# Sheet1.net
KiCad netlist of a schematic drawn in Altium Designer
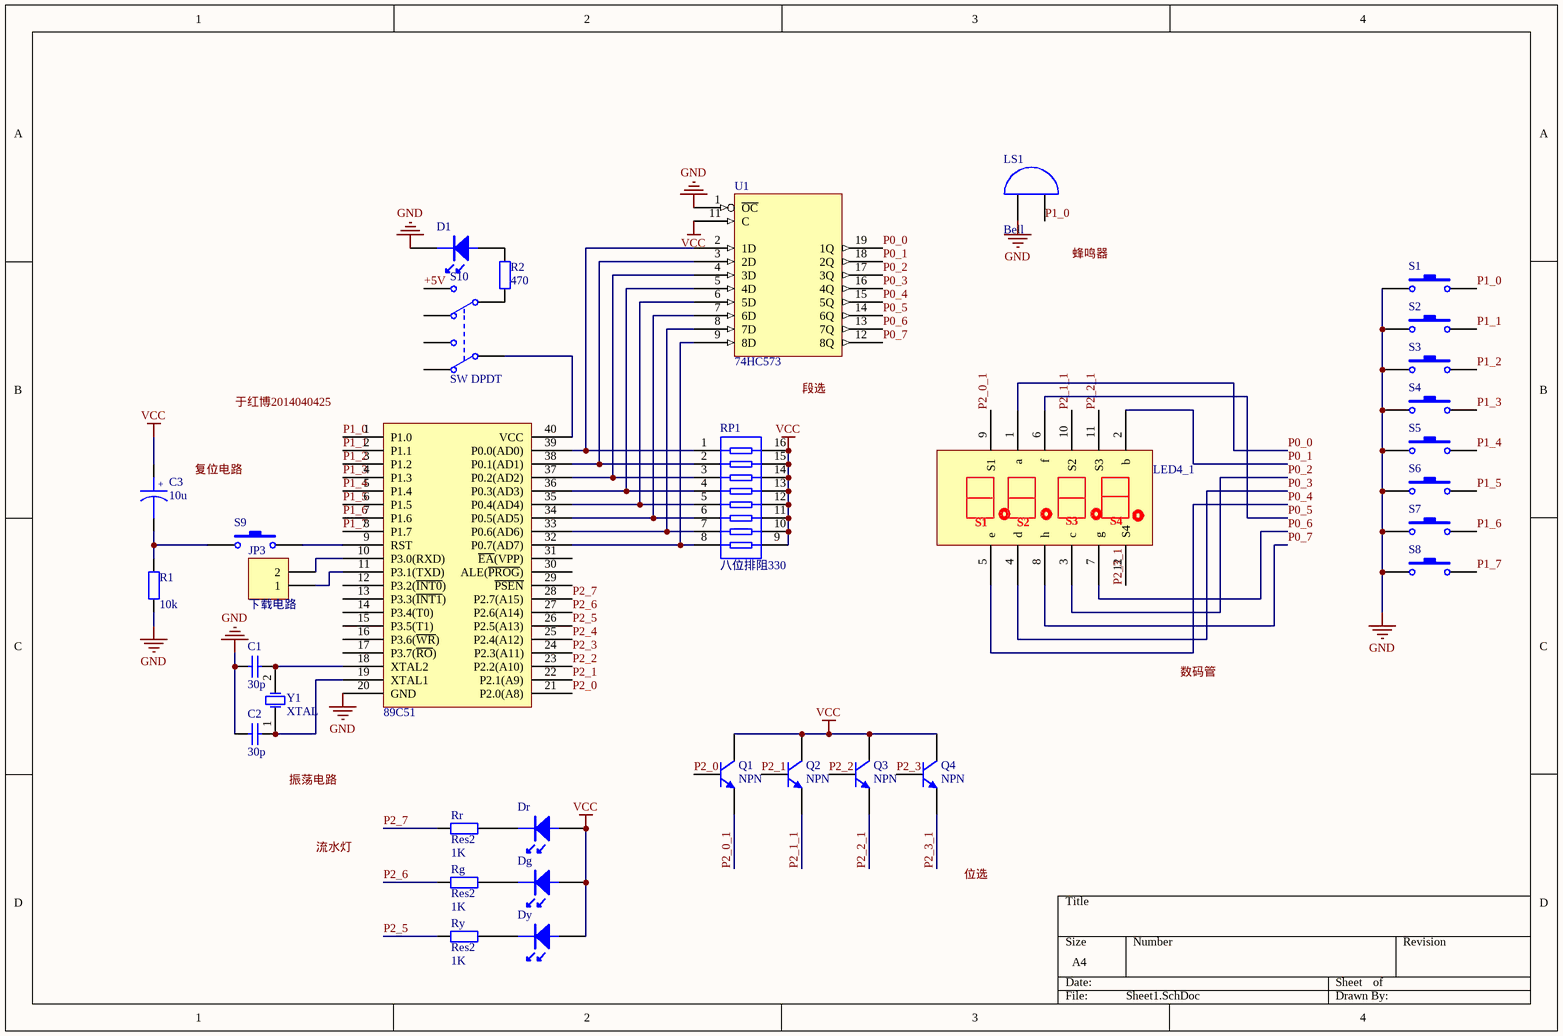
[diagram p0: Sheet1.SchDoc]

(export (version "E")
  (design (tool "Eeschema 10.0.6"))
  (components
    (comp (ref "89c51") (value "89C51") (footprint "DIP40") (libsource (lib "51单片机") (part "89C51")))
    (comp (ref "C1")
      (value "30p")
      (footprint "RAD-0.3")
      (description "Capacitor")
      (fields (field (name "PUBLISHER") "Altium Limited"))
      (libsource (lib "Miscellaneous Devices") (part "Cap"))
    )
    (comp (ref "C2")
      (value "30p")
      (footprint "RAD-0.3")
      (description "Capacitor")
      (fields (field (name "PUBLISHER") "Altium Limited"))
      (libsource (lib "Miscellaneous Devices") (part "Cap"))
    )
    (comp (ref "C3")
      (value "10u")
      (footprint "cap")
      (description "Capacitor")
      (libsource (lib "Integrated_Library1") (part "电解电容"))
    )
    (comp (ref "D1") (value "发光二极管") (footprint "DIODE0.4A") (libsource (lib "二极管") (part "发光二极管")))
    (comp (ref "Dg") (value "发光二极管阵列") (footprint "DIODE0.4A") (libsource (lib "二极管") (part "发光二极管")))
    (comp (ref "Dr") (value "发光二极管阵列") (footprint "DIODE0.4A") (libsource (lib "二极管") (part "发光二极管")))
    (comp (ref "Dy") (value "发光二极管阵列") (footprint "DIODE0.4A") (libsource (lib "二极管") (part "发光二极管")))
    (comp (ref "JP3")
      (value "下载电路")
      (footprint "HDR1X2")
      (description "Header, 2-Pin")
      (fields (field (name "PUBLISHER") "Altium Limited"))
      (libsource (lib "Miscellaneous Connectors") (part "Header 2"))
    )
    (comp (ref "led4") (value "LED4_1") (footprint "HDR2X6") (libsource (lib "数码管") (part "LED4_LWQ")))
    (comp (ref "LS1")
      (value "Bell")
      (footprint "PIN2")
      (description "Electrical Bell")
      (fields (field (name "PUBLISHER") "Altium Limited"))
      (libsource (lib "Miscellaneous Devices") (part "Bell"))
    )
    (comp (ref "Q1")
      (value "NPN")
      (footprint "TO-226-AA")
      (description "NPN Bipolar Transistor")
      (fields (field (name "PUBLISHER") "Altium Limited"))
      (libsource (lib "Miscellaneous Devices") (part "NPN"))
    )
    (comp (ref "Q2")
      (value "NPN")
      (footprint "TO-226-AA")
      (description "NPN Bipolar Transistor")
      (fields (field (name "PUBLISHER") "Altium Limited"))
      (libsource (lib "Miscellaneous Devices") (part "NPN"))
    )
    (comp (ref "Q3")
      (value "NPN")
      (footprint "TO-226-AA")
      (description "NPN Bipolar Transistor")
      (fields (field (name "PUBLISHER") "Altium Limited"))
      (libsource (lib "Miscellaneous Devices") (part "NPN"))
    )
    (comp (ref "Q4")
      (value "NPN")
      (footprint "TO-226-AA")
      (description "NPN Bipolar Transistor")
      (fields (field (name "PUBLISHER") "Altium Limited"))
      (libsource (lib "Miscellaneous Devices") (part "NPN"))
    )
    (comp (ref "R1")
      (value "10k")
      (footprint "AXIAL-0.4")
      (description "Resistor")
      (fields (field (name "Comment") "R1") (field (name "PUBLISHER") "Altium Limited"))
      (libsource (lib "") (part "Res2_1"))
    )
    (comp (ref "R2")
      (value "470")
      (footprint "AXIAL-0.4")
      (description "Resistor")
      (fields (field (name "PUBLISHER") "Altium Limited"))
      (libsource (lib "") (part "Res2_2"))
    )
    (comp (ref "Rg")
      (value "Res2")
      (footprint "AXIAL-0.4")
      (description "Resistor")
      (fields (field (name "ALTIUM_VALUE") "1K") (field (name "PUBLISHER") "Altium Limited"))
      (libsource (lib "Miscellaneous Devices") (part "Res2"))
    )
    (comp (ref "RP1") (value "八位排阻330") (footprint "DIP16") (libsource (lib "电阻") (part "RESPACK4")))
    (comp (ref "Rr")
      (value "Res2")
      (footprint "AXIAL-0.4")
      (description "Resistor")
      (fields (field (name "ALTIUM_VALUE") "1K") (field (name "PUBLISHER") "Altium Limited"))
      (libsource (lib "Miscellaneous Devices") (part "Res2"))
    )
    (comp (ref "Ry")
      (value "Res2")
      (footprint "AXIAL-0.4")
      (description "Resistor")
      (fields (field (name "ALTIUM_VALUE") "1K") (field (name "PUBLISHER") "Altium Limited"))
      (libsource (lib "Miscellaneous Devices") (part "Res2"))
    )
    (comp (ref "S1")
      (value "SW-PB")
      (footprint "SPST-2")
      (description "Switch")
      (fields (field (name "PUBLISHER") "Altium Limited"))
      (libsource (lib "Miscellaneous Devices") (part "SW-PB"))
    )
    (comp (ref "S2")
      (value "SW-PB")
      (footprint "SPST-2")
      (description "Switch")
      (fields (field (name "PUBLISHER") "Altium Limited"))
      (libsource (lib "Miscellaneous Devices") (part "SW-PB"))
    )
    (comp (ref "S3")
      (value "SW-PB")
      (footprint "SPST-2")
      (description "Switch")
      (fields (field (name "PUBLISHER") "Altium Limited"))
      (libsource (lib "Miscellaneous Devices") (part "SW-PB"))
    )
    (comp (ref "S4")
      (value "SW-PB")
      (footprint "SPST-2")
      (description "Switch")
      (fields (field (name "PUBLISHER") "Altium Limited"))
      (libsource (lib "Miscellaneous Devices") (part "SW-PB"))
    )
    (comp (ref "S5")
      (value "SW-PB")
      (footprint "SPST-2")
      (description "Switch")
      (fields (field (name "PUBLISHER") "Altium Limited"))
      (libsource (lib "Miscellaneous Devices") (part "SW-PB"))
    )
    (comp (ref "S6")
      (value "SW-PB")
      (footprint "SPST-2")
      (description "Switch")
      (fields (field (name "PUBLISHER") "Altium Limited"))
      (libsource (lib "Miscellaneous Devices") (part "SW-PB"))
    )
    (comp (ref "S7")
      (value "SW-PB")
      (footprint "SPST-2")
      (description "Switch")
      (fields (field (name "PUBLISHER") "Altium Limited"))
      (libsource (lib "Miscellaneous Devices") (part "SW-PB"))
    )
    (comp (ref "S8")
      (value "SW-PB")
      (footprint "SPST-2")
      (description "Switch")
      (fields (field (name "PUBLISHER") "Altium Limited"))
      (libsource (lib "Miscellaneous Devices") (part "SW-PB"))
    )
    (comp (ref "S9")
      (value "SW-PB")
      (footprint "SPST-2")
      (description "Switch")
      (fields (field (name "PUBLISHER") "Altium Limited"))
      (libsource (lib "Miscellaneous Devices") (part "SW-PB"))
    )
    (comp (ref "S10")
      (value "SW DPDT")
      (footprint "SOT23-6_N")
      (description "Switch")
      (fields (field (name "PUBLISHER") "Altium Limited"))
      (libsource (lib "Miscellaneous Devices") (part "SW DPDT"))
    )
    (comp (ref "U1") (value "74HC573") (footprint "DIP-20") (libsource (lib "TTL74系列IC") (part "74HC573")))
    (comp (ref "Y1")
      (value "XTAL")
      (footprint "R38")
      (description "Crystal Oscillator")
      (fields (field (name "PUBLISHER") "Altium Limited"))
      (libsource (lib "Miscellaneous Devices") (part "XTAL"))
    )
  )
  (nets
    (net (code "1") (name "/+5V") (class "Default")
      (node (ref "S10") (pin "6") (pinfunction "NO2_6") (pintype "passive"))
    )
    (net (code "2") (name "/P0_0") (class "Default")
      (node (ref "U1") (pin "19") (pinfunction "1Q_19") (pintype "output"))
      (node (ref "led4") (pin "1") (pinfunction "a_1") (pintype "passive"))
    )
    (net (code "3") (name "/P0_1") (class "Default")
      (node (ref "U1") (pin "18") (pinfunction "2Q_18") (pintype "output"))
      (node (ref "led4") (pin "2") (pinfunction "b_2") (pintype "passive"))
    )
    (net (code "4") (name "/P0_2") (class "Default")
      (node (ref "U1") (pin "17") (pinfunction "3Q_17") (pintype "output"))
      (node (ref "led4") (pin "3") (pinfunction "c_3") (pintype "passive"))
    )
    (net (code "5") (name "/P0_3") (class "Default")
      (node (ref "U1") (pin "16") (pinfunction "4Q_16") (pintype "output"))
      (node (ref "led4") (pin "4") (pinfunction "d_4") (pintype "passive"))
    )
    (net (code "6") (name "/P0_4") (class "Default")
      (node (ref "U1") (pin "15") (pinfunction "5Q_15") (pintype "output"))
      (node (ref "led4") (pin "5") (pinfunction "e_5") (pintype "passive"))
    )
    (net (code "7") (name "/P0_5") (class "Default")
      (node (ref "U1") (pin "14") (pinfunction "6Q_14") (pintype "output"))
      (node (ref "led4") (pin "6") (pinfunction "f_6") (pintype "passive"))
    )
    (net (code "8") (name "/P0_6") (class "Default")
      (node (ref "U1") (pin "13") (pinfunction "7Q_13") (pintype "output"))
      (node (ref "led4") (pin "7") (pinfunction "g_7") (pintype "passive"))
    )
    (net (code "9") (name "/P0_7") (class "Default")
      (node (ref "U1") (pin "12") (pinfunction "8Q_12") (pintype "output"))
      (node (ref "led4") (pin "8") (pinfunction "h_8") (pintype "passive"))
    )
    (net (code "10") (name "/P1_0") (class "Default")
      (node (ref "89c51") (pin "1") (pinfunction "P1.0_1") (pintype "passive"))
      (node (ref "LS1") (pin "2") (pinfunction "B_2") (pintype "passive"))
      (node (ref "S1") (pin "2") (pinfunction "2_2") (pintype "passive"))
    )
    (net (code "11") (name "/P1_1") (class "Default")
      (node (ref "89c51") (pin "2") (pinfunction "P1.1_2") (pintype "passive"))
      (node (ref "S2") (pin "2") (pinfunction "2_2") (pintype "passive"))
    )
    (net (code "12") (name "/P1_2") (class "Default")
      (node (ref "89c51") (pin "3") (pinfunction "P1.2_3") (pintype "passive"))
      (node (ref "S3") (pin "2") (pinfunction "2_2") (pintype "passive"))
    )
    (net (code "13") (name "/P1_3") (class "Default")
      (node (ref "89c51") (pin "4") (pinfunction "P1.3_4") (pintype "passive"))
      (node (ref "S4") (pin "2") (pinfunction "2_2") (pintype "passive"))
    )
    (net (code "14") (name "/P1_4") (class "Default")
      (node (ref "89c51") (pin "5") (pinfunction "P1.4_5") (pintype "passive"))
      (node (ref "S5") (pin "2") (pinfunction "2_2") (pintype "passive"))
    )
    (net (code "15") (name "/P1_5") (class "Default")
      (node (ref "89c51") (pin "6") (pinfunction "P1.5_6") (pintype "passive"))
      (node (ref "S6") (pin "2") (pinfunction "2_2") (pintype "passive"))
    )
    (net (code "16") (name "/P1_6") (class "Default")
      (node (ref "89c51") (pin "7") (pinfunction "P1.6_7") (pintype "passive"))
      (node (ref "S7") (pin "2") (pinfunction "2_2") (pintype "passive"))
    )
    (net (code "17") (name "/P1_7") (class "Default")
      (node (ref "89c51") (pin "8") (pinfunction "P1.7_8") (pintype "passive"))
      (node (ref "S8") (pin "2") (pinfunction "2_2") (pintype "passive"))
    )
    (net (code "18") (name "/P2_0") (class "Default")
      (node (ref "89c51") (pin "21") (pinfunction "P2.0(A8)_21") (pintype "passive"))
      (node (ref "Q1") (pin "2") (pinfunction "B_2") (pintype "passive"))
    )
    (net (code "19") (name "/P2_0_1") (class "Default")
      (node (ref "Q1") (pin "3") (pinfunction "E_3") (pintype "passive"))
      (node (ref "led4") (pin "9") (pinfunction "S1_9") (pintype "passive"))
    )
    (net (code "20") (name "/P2_1") (class "Default")
      (node (ref "89c51") (pin "22") (pinfunction "P2.1(A9)_22") (pintype "passive"))
      (node (ref "Q2") (pin "2") (pinfunction "B_2") (pintype "passive"))
    )
    (net (code "21") (name "/P2_1_1") (class "Default")
      (node (ref "Q2") (pin "3") (pinfunction "E_3") (pintype "passive"))
      (node (ref "led4") (pin "10") (pinfunction "S2_10") (pintype "passive"))
    )
    (net (code "22") (name "/P2_2") (class "Default")
      (node (ref "89c51") (pin "23") (pinfunction "P2.2(A10)_23") (pintype "passive"))
      (node (ref "Q3") (pin "2") (pinfunction "B_2") (pintype "passive"))
    )
    (net (code "23") (name "/P2_2_1") (class "Default")
      (node (ref "Q3") (pin "3") (pinfunction "E_3") (pintype "passive"))
      (node (ref "led4") (pin "11") (pinfunction "S3_11") (pintype "passive"))
    )
    (net (code "24") (name "/P2_3") (class "Default")
      (node (ref "89c51") (pin "24") (pinfunction "P2.3(A11)_24") (pintype "passive"))
      (node (ref "Q4") (pin "2") (pinfunction "B_2") (pintype "passive"))
    )
    (net (code "25") (name "/P2_3_1") (class "Default")
      (node (ref "Q4") (pin "3") (pinfunction "E_3") (pintype "passive"))
      (node (ref "led4") (pin "12") (pinfunction "S4_12") (pintype "passive"))
    )
    (net (code "26") (name "/P2_4") (class "Default")
      (node (ref "89c51") (pin "25") (pinfunction "P2.4(A12)_25") (pintype "passive"))
    )
    (net (code "27") (name "/P2_5") (class "Default")
      (node (ref "89c51") (pin "26") (pinfunction "P2.5(A13)_26") (pintype "passive"))
      (node (ref "Ry") (pin "1") (pinfunction "1_1") (pintype "passive"))
    )
    (net (code "28") (name "/P2_6") (class "Default")
      (node (ref "89c51") (pin "27") (pinfunction "P2.6(A14)_27") (pintype "passive"))
      (node (ref "Rg") (pin "1") (pinfunction "1_1") (pintype "passive"))
    )
    (net (code "29") (name "/P2_7") (class "Default")
      (node (ref "89c51") (pin "28") (pinfunction "P2.7(A15)_28") (pintype "passive"))
      (node (ref "Rr") (pin "1") (pinfunction "1_1") (pintype "passive"))
    )
    (net (code "38") (name "GND") (class "Default")
      (node (ref "89c51") (pin "20") (pinfunction "GND_20") (pintype "passive"))
      (node (ref "C1") (pin "1") (pinfunction "1_1") (pintype "passive"))
      (node (ref "C2") (pin "1") (pinfunction "1_1") (pintype "passive"))
      (node (ref "D1") (pin "K") (pinfunction "2_K") (pintype "passive"))
      (node (ref "LS1") (pin "1") (pinfunction "A_1") (pintype "passive"))
      (node (ref "R1") (pin "1") (pinfunction "1_1") (pintype "passive"))
      (node (ref "S1") (pin "1") (pinfunction "1_1") (pintype "passive"))
      (node (ref "S2") (pin "1") (pinfunction "1_1") (pintype "passive"))
      (node (ref "S3") (pin "1") (pinfunction "1_1") (pintype "passive"))
      (node (ref "S4") (pin "1") (pinfunction "1_1") (pintype "passive"))
      (node (ref "S5") (pin "1") (pinfunction "1_1") (pintype "passive"))
      (node (ref "S6") (pin "1") (pinfunction "1_1") (pintype "passive"))
      (node (ref "S7") (pin "1") (pinfunction "1_1") (pintype "passive"))
      (node (ref "S8") (pin "1") (pinfunction "1_1") (pintype "passive"))
      (node (ref "U1") (pin "1") (pinfunction "~{OC}_1") (pintype "input"))
      (node (ref "U1") (pin "10") (pinfunction "GND_10") (pintype "power_in"))
    )
    (net (code "39") (name "Net-(89c51-P0.0(AD0))") (class "Default")
      (node (ref "89c51") (pin "39") (pinfunction "P0.0(AD0)_39") (pintype "passive"))
      (node (ref "RP1") (pin "1") (pinfunction "1_1") (pintype "passive"))
      (node (ref "U1") (pin "2") (pinfunction "1D_2") (pintype "input"))
    )
    (net (code "40") (name "Net-(89c51-P0.1(AD1))") (class "Default")
      (node (ref "89c51") (pin "38") (pinfunction "P0.1(AD1)_38") (pintype "passive"))
      (node (ref "RP1") (pin "2") (pinfunction "2_2") (pintype "passive"))
      (node (ref "U1") (pin "3") (pinfunction "2D_3") (pintype "input"))
    )
    (net (code "41") (name "Net-(89c51-P0.2(AD2))") (class "Default")
      (node (ref "89c51") (pin "37") (pinfunction "P0.2(AD2)_37") (pintype "passive"))
      (node (ref "RP1") (pin "3") (pinfunction "3_3") (pintype "passive"))
      (node (ref "U1") (pin "4") (pinfunction "3D_4") (pintype "input"))
    )
    (net (code "42") (name "Net-(89c51-P0.3(AD3))") (class "Default")
      (node (ref "89c51") (pin "36") (pinfunction "P0.3(AD3)_36") (pintype "passive"))
      (node (ref "RP1") (pin "4") (pinfunction "4_4") (pintype "passive"))
      (node (ref "U1") (pin "5") (pinfunction "4D_5") (pintype "input"))
    )
    (net (code "43") (name "Net-(89c51-P0.4(AD4))") (class "Default")
      (node (ref "89c51") (pin "35") (pinfunction "P0.4(AD4)_35") (pintype "passive"))
      (node (ref "RP1") (pin "5") (pinfunction "5_5") (pintype "passive"))
      (node (ref "U1") (pin "6") (pinfunction "5D_6") (pintype "input"))
    )
    (net (code "44") (name "Net-(89c51-P0.5(AD5))") (class "Default")
      (node (ref "89c51") (pin "34") (pinfunction "P0.5(AD5)_34") (pintype "passive"))
      (node (ref "RP1") (pin "6") (pinfunction "6_6") (pintype "passive"))
      (node (ref "U1") (pin "7") (pinfunction "6D_7") (pintype "input"))
    )
    (net (code "45") (name "Net-(89c51-P0.6(AD6))") (class "Default")
      (node (ref "89c51") (pin "33") (pinfunction "P0.6(AD6)_33") (pintype "passive"))
      (node (ref "RP1") (pin "7") (pinfunction "7_7") (pintype "passive"))
      (node (ref "U1") (pin "8") (pinfunction "7D_8") (pintype "input"))
    )
    (net (code "46") (name "Net-(89c51-P0.7(AD7))") (class "Default")
      (node (ref "89c51") (pin "32") (pinfunction "P0.7(AD7)_32") (pintype "passive"))
      (node (ref "RP1") (pin "8") (pinfunction "8_8") (pintype "passive"))
      (node (ref "U1") (pin "9") (pinfunction "8D_9") (pintype "input"))
    )
    (net (code "47") (name "Net-(89c51-P3.0(RXD))") (class "Default")
      (node (ref "89c51") (pin "10") (pinfunction "P3.0(RXD)_10") (pintype "passive"))
      (node (ref "JP3") (pin "2") (pinfunction "2_2") (pintype "passive"))
    )
    (net (code "48") (name "Net-(89c51-P3.1(TXD))") (class "Default")
      (node (ref "89c51") (pin "11") (pinfunction "P3.1(TXD)_11") (pintype "passive"))
      (node (ref "JP3") (pin "1") (pinfunction "1_1") (pintype "passive"))
    )
    (net (code "49") (name "Net-(89c51-RST)") (class "Default")
      (node (ref "89c51") (pin "9") (pinfunction "RST_9") (pintype "passive"))
      (node (ref "S9") (pin "2") (pinfunction "2_2") (pintype "passive"))
    )
    (net (code "50") (name "Net-(89c51-VCC)") (class "Default")
      (node (ref "89c51") (pin "40") (pinfunction "VCC_40") (pintype "passive"))
      (node (ref "S10") (pin "1") (pinfunction "COMMON1_1") (pintype "passive"))
    )
    (net (code "51") (name "Net-(89c51-XTAL1)") (class "Default")
      (node (ref "89c51") (pin "19") (pinfunction "XTAL1_19") (pintype "passive"))
      (node (ref "C2") (pin "2") (pinfunction "2_2") (pintype "passive"))
      (node (ref "Y1") (pin "1") (pinfunction "OSC1_1") (pintype "passive"))
    )
    (net (code "52") (name "Net-(89c51-XTAL2)") (class "Default")
      (node (ref "89c51") (pin "18") (pinfunction "XTAL2_18") (pintype "passive"))
      (node (ref "C1") (pin "2") (pinfunction "2_2") (pintype "passive"))
      (node (ref "Y1") (pin "2") (pinfunction "OSC2_2") (pintype "passive"))
    )
    (net (code "53") (name "Net-(C3-Pad2)") (class "Default")
      (node (ref "C3") (pin "2") (pinfunction "2_2") (pintype "passive"))
      (node (ref "R1") (pin "2") (pinfunction "2_2") (pintype "passive"))
      (node (ref "S9") (pin "1") (pinfunction "1_1") (pintype "passive"))
    )
    (net (code "54") (name "Net-(D1-1)") (class "Default")
      (node (ref "D1") (pin "A") (pinfunction "1_A") (pintype "passive"))
      (node (ref "R2") (pin "1") (pinfunction "1_1") (pintype "passive"))
    )
    (net (code "55") (name "Net-(Dg-2)") (class "Default")
      (node (ref "Dg") (pin "K") (pinfunction "2_K") (pintype "passive"))
      (node (ref "Rg") (pin "2") (pinfunction "2_2") (pintype "passive"))
    )
    (net (code "56") (name "Net-(Dr-2)") (class "Default")
      (node (ref "Dr") (pin "K") (pinfunction "2_K") (pintype "passive"))
      (node (ref "Rr") (pin "2") (pinfunction "2_2") (pintype "passive"))
    )
    (net (code "57") (name "Net-(Dy-2)") (class "Default")
      (node (ref "Dy") (pin "K") (pinfunction "2_K") (pintype "passive"))
      (node (ref "Ry") (pin "2") (pinfunction "2_2") (pintype "passive"))
    )
    (net (code "58") (name "Net-(S10-COMMON2)") (class "Default")
      (node (ref "R2") (pin "2") (pinfunction "2_2") (pintype "passive"))
      (node (ref "S10") (pin "5") (pinfunction "COMMON2_5") (pintype "passive"))
    )
    (net (code "59") (name "VCC") (class "Default")
      (node (ref "C3") (pin "1") (pinfunction "1_1") (pintype "passive"))
      (node (ref "Dg") (pin "A") (pinfunction "1_A") (pintype "passive"))
      (node (ref "Dr") (pin "A") (pinfunction "1_A") (pintype "passive"))
      (node (ref "Dy") (pin "A") (pinfunction "1_A") (pintype "passive"))
      (node (ref "Q1") (pin "1") (pinfunction "C_1") (pintype "passive"))
      (node (ref "Q2") (pin "1") (pinfunction "C_1") (pintype "passive"))
      (node (ref "Q3") (pin "1") (pinfunction "C_1") (pintype "passive"))
      (node (ref "Q4") (pin "1") (pinfunction "C_1") (pintype "passive"))
      (node (ref "RP1") (pin "10") (pinfunction "10_10") (pintype "passive"))
      (node (ref "RP1") (pin "11") (pinfunction "11_11") (pintype "passive"))
      (node (ref "RP1") (pin "12") (pinfunction "12_12") (pintype "passive"))
      (node (ref "RP1") (pin "13") (pinfunction "13_13") (pintype "passive"))
      (node (ref "RP1") (pin "14") (pinfunction "14_14") (pintype "passive"))
      (node (ref "RP1") (pin "15") (pinfunction "15_15") (pintype "passive"))
      (node (ref "RP1") (pin "16") (pinfunction "16_16") (pintype "passive"))
      (node (ref "RP1") (pin "9") (pinfunction "9_9") (pintype "passive"))
      (node (ref "U1") (pin "11") (pinfunction "C_11") (pintype "input"))
      (node (ref "U1") (pin "20") (pinfunction "VCC_20") (pintype "power_in"))
    )
    (net (code "60") (name "unconnected-(89c51-ALE(~{PROG})-Pad30)") (class "Default")
      (node (ref "89c51") (pin "30") (pinfunction "ALE(~{PROG})_30") (pintype "passive"))
    )
    (net (code "61") (name "unconnected-(89c51-P3.2(~{INT0})-Pad12)") (class "Default")
      (node (ref "89c51") (pin "12") (pinfunction "P3.2(~{INT0})_12") (pintype "passive"))
    )
    (net (code "62") (name "unconnected-(89c51-P3.3(~{INT1})-Pad13)") (class "Default")
      (node (ref "89c51") (pin "13") (pinfunction "P3.3(~{INT1})_13") (pintype "passive"))
    )
    (net (code "63") (name "unconnected-(89c51-P3.4(T0)-Pad14)") (class "Default")
      (node (ref "89c51") (pin "14") (pinfunction "P3.4(T0)_14") (pintype "passive"))
    )
    (net (code "64") (name "unconnected-(89c51-P3.5(T1)-Pad15)") (class "Default")
      (node (ref "89c51") (pin "15") (pinfunction "P3.5(T1)_15") (pintype "passive"))
    )
    (net (code "65") (name "unconnected-(89c51-P3.6(~{WR})-Pad16)") (class "Default")
      (node (ref "89c51") (pin "16") (pinfunction "P3.6(~{WR})_16") (pintype "passive"))
    )
    (net (code "66") (name "unconnected-(89c51-P3.7(~{RO})-Pad17)") (class "Default")
      (node (ref "89c51") (pin "17") (pinfunction "P3.7(~{RO})_17") (pintype "passive"))
    )
    (net (code "67") (name "unconnected-(89c51-~{EA}(VPP)-Pad31)") (class "Default")
      (node (ref "89c51") (pin "31") (pinfunction "~{EA}(VPP)_31") (pintype "passive"))
    )
    (net (code "68") (name "unconnected-(89c51-~{PSEN}-Pad29)") (class "Default")
      (node (ref "89c51") (pin "29") (pinfunction "~{PSEN}_29") (pintype "passive"))
    )
    (net (code "69") (name "unconnected-(S10-NC1-Pad2)") (class "Default")
      (node (ref "S10") (pin "2") (pinfunction "NC1_2") (pintype "passive"))
    )
    (net (code "70") (name "unconnected-(S10-NC2-Pad4)") (class "Default")
      (node (ref "S10") (pin "4") (pinfunction "NC2_4") (pintype "passive"))
    )
    (net (code "71") (name "unconnected-(S10-NO1-Pad3)") (class "Default")
      (node (ref "S10") (pin "3") (pinfunction "NO1_3") (pintype "passive"))
    )
  )
)
